# halloween-grave-bell-v02.net
KiCad netlist of a schematic drawn in EAGLE
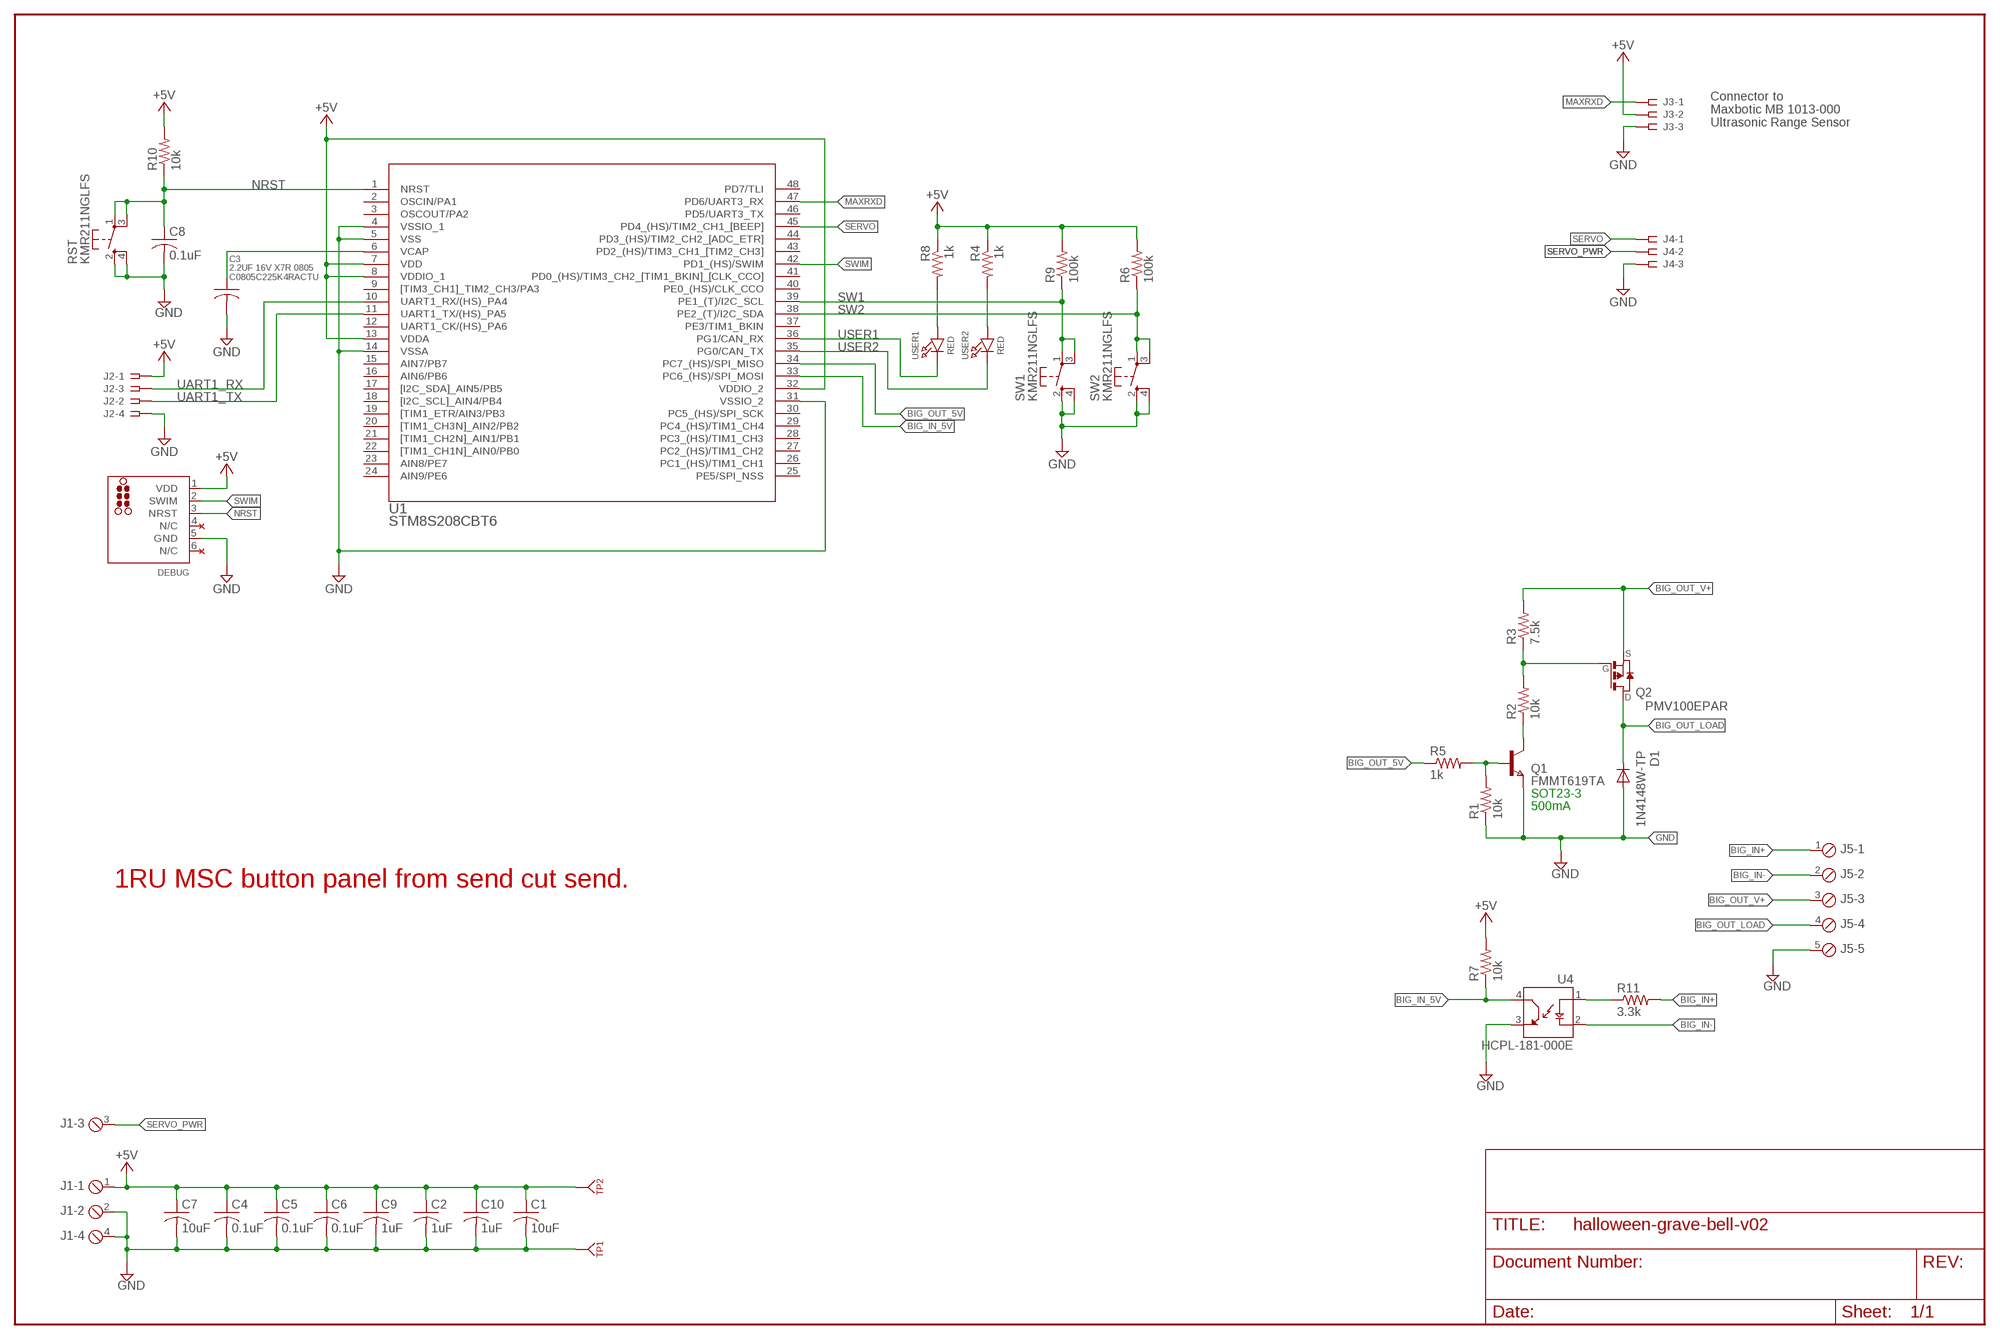
[diagram p0: schematic, sheet 1]

(export (version "E")
  (design (tool "Eeschema 10.0.6"))
  (components
    (comp (ref "C1")
      (value "10uF")
      (footprint "eagle-import:C1210")
      (fields (field (name "MFR") "KEMET") (field (name "MFR_PART_NO") "C1210C105K4PACTU"))
      (libsource (lib "eagle-import") (part "C-USC1210"))
    )
    (comp (ref "C2")
      (value "1uF")
      (footprint "eagle-import:C0603")
      (libsource (lib "eagle-import") (part "C-USC0603"))
    )
    (comp (ref "C3")
      (value "2.2UF 16V X7R 0805")
      (footprint "eagle-import:C0805")
      (fields (field (name "MFR_PART_NUM") "C0805C225K4RACTU"))
      (libsource (lib "eagle-import") (part "resistor_C-USC0805"))
    )
    (comp (ref "C4")
      (value "0.1uF")
      (footprint "eagle-import:C0603")
      (libsource (lib "eagle-import") (part "C-USC0603"))
    )
    (comp (ref "C5")
      (value "0.1uF")
      (footprint "eagle-import:C0603")
      (libsource (lib "eagle-import") (part "C-USC0603"))
    )
    (comp (ref "C6")
      (value "0.1uF")
      (footprint "eagle-import:C0603")
      (libsource (lib "eagle-import") (part "C-USC0603"))
    )
    (comp (ref "C7")
      (value "10uF")
      (footprint "eagle-import:C1210")
      (fields (field (name "MFR") "KEMET") (field (name "MFR_PART_NO") "C1210C105K4PACTU"))
      (libsource (lib "eagle-import") (part "C-USC1210"))
    )
    (comp (ref "C8")
      (value "0.1uF")
      (footprint "eagle-import:C0805")
      (libsource (lib "eagle-import") (part "C-USC0805"))
    )
    (comp (ref "C9")
      (value "1uF")
      (footprint "eagle-import:C0603")
      (libsource (lib "eagle-import") (part "C-USC0603"))
    )
    (comp (ref "C10")
      (value "1uF")
      (footprint "eagle-import:C0603")
      (libsource (lib "eagle-import") (part "C-USC0603"))
    )
    (comp (ref "D1")
      (value "1N4148W-TP")
      (footprint "eagle-import:SOD123")
      (libsource (lib "eagle-import") (part "DIODE-SOD123"))
    )
    (comp (ref "DEBUG")
      (value "TC2030-NL-STM8")
      (footprint "eagle-import:TC2030-NL")
      (libsource (lib "eagle-import") (part "TC2030-NL-STM8"))
    )
    (comp (ref "J1")
      (value "MPT4")
      (footprint "eagle-import:4POL254")
      (libsource (lib "eagle-import") (part "MPT4"))
    )
    (comp (ref "J2")
      (value "SSW-104-02-S-S")
      (footprint "eagle-import:SSW-104-02-S-S")
      (libsource (lib "eagle-import") (part "SSW-104-02-S-S"))
    )
    (comp (ref "J3")
      (value "SSW-103-02-S-S")
      (footprint "eagle-import:SSW-103-02-S-S")
      (libsource (lib "eagle-import") (part "SSW-103-02-S-S"))
    )
    (comp (ref "J4")
      (value "SSW-103-02-S-S")
      (footprint "eagle-import:SSW-103-02-S-S")
      (libsource (lib "eagle-import") (part "SSW-103-02-S-S"))
    )
    (comp (ref "J5")
      (value "MPT5")
      (footprint "eagle-import:5POL254")
      (libsource (lib "eagle-import") (part "MPT5"))
    )
    (comp (ref "Q1")
      (value "FMMT619TA")
      (footprint "eagle-import:SOT-23")
      (fields (field (name "MPN") "DSS20201L-7"))
      (libsource (lib "eagle-import") (part "NPNSOT23"))
    )
    (comp (ref "Q2")
      (value "PMOSSOT23")
      (footprint "eagle-import:SOT-23")
      (libsource (lib "eagle-import") (part "PMOSSOT23"))
    )
    (comp (ref "R1")
      (value "10k")
      (footprint "eagle-import:R0603")
      (libsource (lib "eagle-import") (part "R-US_R0603"))
    )
    (comp (ref "R2")
      (value "10k")
      (footprint "eagle-import:R0603")
      (libsource (lib "eagle-import") (part "R-US_R0603"))
    )
    (comp (ref "R3")
      (value "7.5k")
      (footprint "eagle-import:R0603")
      (libsource (lib "eagle-import") (part "R-US_R0603"))
    )
    (comp (ref "R4")
      (value "1k")
      (footprint "eagle-import:R0805")
      (libsource (lib "eagle-import") (part "R-US_R0805"))
    )
    (comp (ref "R5")
      (value "1k")
      (footprint "eagle-import:R0603")
      (libsource (lib "eagle-import") (part "R-US_R0603"))
    )
    (comp (ref "R6")
      (value "100k")
      (footprint "eagle-import:R0805")
      (libsource (lib "eagle-import") (part "R-US_R0805"))
    )
    (comp (ref "R7")
      (value "10k")
      (footprint "eagle-import:R0603")
      (libsource (lib "eagle-import") (part "R-US_R0603"))
    )
    (comp (ref "R8")
      (value "1k")
      (footprint "eagle-import:R0805")
      (libsource (lib "eagle-import") (part "R-US_R0805"))
    )
    (comp (ref "R9")
      (value "100k")
      (footprint "eagle-import:R0805")
      (libsource (lib "eagle-import") (part "R-US_R0805"))
    )
    (comp (ref "R10")
      (value "10k")
      (footprint "eagle-import:R0805")
      (libsource (lib "eagle-import") (part "R-US_R0805"))
    )
    (comp (ref "R11")
      (value "3.3k")
      (footprint "eagle-import:R0603")
      (libsource (lib "eagle-import") (part "R-US_R0603"))
    )
    (comp (ref "RST")
      (value "KMR211NGLFS")
      (footprint "eagle-import:KMR2")
      (libsource (lib "eagle-import") (part "SPST_TACT-KMR2"))
    )
    (comp (ref "SW1")
      (value "KMR211NGLFS")
      (footprint "eagle-import:KMR2")
      (libsource (lib "eagle-import") (part "SPST_TACT-KMR2"))
    )
    (comp (ref "SW2")
      (value "KMR211NGLFS")
      (footprint "eagle-import:KMR2")
      (libsource (lib "eagle-import") (part "SPST_TACT-KMR2"))
    )
    (comp (ref "TP1")
      (value "KEYSTONE_500X")
      (footprint "eagle-import:KEYSTONE_TP500X")
      (libsource (lib "eagle-import") (part "KEYSTONE_500X"))
    )
    (comp (ref "TP2")
      (value "KEYSTONE_500X")
      (footprint "eagle-import:KEYSTONE_TP500X")
      (libsource (lib "eagle-import") (part "KEYSTONE_500X"))
    )
    (comp (ref "U1")
      (value "STM8S208CBT6")
      (footprint "eagle-import:LQFP-48_STM")
      (libsource (lib "eagle-import") (part "STM8S208CBT6"))
    )
    (comp (ref "U4")
      (value "HCPL-181-000E")
      (footprint "eagle-import:SOIC254P675X240-4N")
      (fields (field (name "DIGI-KEY_PART_NUMBER") "516-1646-1-ND") (field (name "MF") "Broadcom Limited"))
      (libsource (lib "eagle-import") (part "HCPL-181-000E"))
    )
    (comp (ref "USER1")
      (value "RED")
      (footprint "eagle-import:CHIPLED_0805_NOOUTLINE")
      (libsource (lib "eagle-import") (part "LED0805_NOOUTLINE"))
    )
    (comp (ref "USER2")
      (value "RED")
      (footprint "eagle-import:CHIPLED_0805_NOOUTLINE")
      (libsource (lib "eagle-import") (part "LED0805_NOOUTLINE"))
    )
  )
  (nets
    (net (code "1") (name "+5V") (class "Default")
      (node (ref "C1") (pin "1") (pinfunction "1_1") (pintype "passive"))
      (node (ref "C10") (pin "1") (pinfunction "1_1") (pintype "passive"))
      (node (ref "C2") (pin "1") (pinfunction "1_1") (pintype "passive"))
      (node (ref "C4") (pin "1") (pinfunction "1_1") (pintype "passive"))
      (node (ref "C5") (pin "1") (pinfunction "1_1") (pintype "passive"))
      (node (ref "C6") (pin "1") (pinfunction "1_1") (pintype "passive"))
      (node (ref "C7") (pin "1") (pinfunction "1_1") (pintype "passive"))
      (node (ref "C9") (pin "1") (pinfunction "1_1") (pintype "passive"))
      (node (ref "DEBUG") (pin "1") (pinfunction "VDD_1") (pintype "passive"))
      (node (ref "J1") (pin "1") (pinfunction "1_1") (pintype "passive"))
      (node (ref "J2") (pin "1") (pinfunction "1_1") (pintype "passive"))
      (node (ref "J3") (pin "2") (pinfunction "1_2") (pintype "passive"))
      (node (ref "R10") (pin "2") (pinfunction "2_2") (pintype "passive"))
      (node (ref "R4") (pin "1") (pinfunction "1_1") (pintype "passive"))
      (node (ref "R6") (pin "2") (pinfunction "2_2") (pintype "passive"))
      (node (ref "R7") (pin "2") (pinfunction "2_2") (pintype "passive"))
      (node (ref "R8") (pin "1") (pinfunction "1_1") (pintype "passive"))
      (node (ref "R9") (pin "2") (pinfunction "2_2") (pintype "passive"))
      (node (ref "TP2") (pin "1") (pinfunction "P$1_1") (pintype "bidirectional"))
      (node (ref "U1") (pin "13") (pinfunction "VDDA_13") (pintype "power_in"))
      (node (ref "U1") (pin "32") (pinfunction "VDDIO_2_32") (pintype "power_in"))
      (node (ref "U1") (pin "7") (pinfunction "VDD_7") (pintype "power_in"))
      (node (ref "U1") (pin "8") (pinfunction "VDDIO_1_8") (pintype "power_in"))
    )
    (net (code "2") (name "/SW1") (class "Default")
      (node (ref "R9") (pin "1") (pinfunction "1_1") (pintype "passive"))
      (node (ref "SW1") (pin "1") (pinfunction "P_1") (pintype "passive"))
      (node (ref "SW1") (pin "3") (pinfunction "P1_3") (pintype "passive"))
      (node (ref "U1") (pin "39") (pinfunction "PE1_(T)/I2C_SCL_39") (pintype "bidirectional"))
    )
    (net (code "3") (name "/SW2") (class "Default")
      (node (ref "R6") (pin "1") (pinfunction "1_1") (pintype "passive"))
      (node (ref "SW2") (pin "1") (pinfunction "P_1") (pintype "passive"))
      (node (ref "SW2") (pin "3") (pinfunction "P1_3") (pintype "passive"))
      (node (ref "U1") (pin "38") (pinfunction "PE2_(T)/I2C_SDA_38") (pintype "bidirectional"))
    )
    (net (code "4") (name "/UART1_RX") (class "Default")
      (node (ref "J2") (pin "3") (pinfunction "1_3") (pintype "passive"))
      (node (ref "U1") (pin "10") (pinfunction "UART1_RX/(HS)_PA4_10") (pintype "bidirectional"))
    )
    (net (code "5") (name "/UART1_TX") (class "Default")
      (node (ref "J2") (pin "2") (pinfunction "1_2") (pintype "passive"))
      (node (ref "U1") (pin "11") (pinfunction "UART1_TX/(HS)_PA5_11") (pintype "bidirectional"))
    )
    (net (code "6") (name "/USER1") (class "Default")
      (node (ref "U1") (pin "36") (pinfunction "PG1/CAN_RX_36") (pintype "bidirectional"))
      (node (ref "USER1") (pin "C") (pinfunction "C_C") (pintype "passive"))
    )
    (net (code "7") (name "/USER2") (class "Default")
      (node (ref "U1") (pin "35") (pinfunction "PG0/CAN_TX_35") (pintype "bidirectional"))
      (node (ref "USER2") (pin "C") (pinfunction "C_C") (pintype "passive"))
    )
    (net (code "8") (name "BIG_IN+") (class "Default")
      (node (ref "J5") (pin "1") (pinfunction "1_1") (pintype "passive"))
      (node (ref "R11") (pin "2") (pinfunction "2_2") (pintype "passive"))
    )
    (net (code "9") (name "BIG_IN-") (class "Default")
      (node (ref "J5") (pin "2") (pinfunction "1_2") (pintype "passive"))
      (node (ref "U4") (pin "2") (pinfunction "CATHODE_2") (pintype "passive"))
    )
    (net (code "10") (name "BIG_IN_5V") (class "Default")
      (node (ref "R7") (pin "1") (pinfunction "1_1") (pintype "passive"))
      (node (ref "U1") (pin "33") (pinfunction "PC6_(HS)/SPI_MOSI_33") (pintype "bidirectional"))
      (node (ref "U4") (pin "4") (pinfunction "COLLECTOR_4") (pintype "passive"))
    )
    (net (code "11") (name "BIG_OUT_5V") (class "Default")
      (node (ref "R5") (pin "1") (pinfunction "1_1") (pintype "passive"))
      (node (ref "U1") (pin "34") (pinfunction "PC7_(HS)/SPI_MISO_34") (pintype "bidirectional"))
    )
    (net (code "12") (name "BIG_OUT_LOAD") (class "Default")
      (node (ref "D1") (pin "C") (pinfunction "C_C") (pintype "passive"))
      (node (ref "J5") (pin "4") (pinfunction "1_4") (pintype "passive"))
      (node (ref "Q2") (pin "1") (pinfunction "D_1") (pintype "passive"))
    )
    (net (code "13") (name "BIG_OUT_V+") (class "Default")
      (node (ref "J5") (pin "3") (pinfunction "1_3") (pintype "passive"))
      (node (ref "Q2") (pin "2") (pinfunction "S_2") (pintype "passive"))
      (node (ref "R3") (pin "2") (pinfunction "2_2") (pintype "passive"))
    )
    (net (code "14") (name "GND") (class "Default")
      (node (ref "C1") (pin "2") (pinfunction "2_2") (pintype "passive"))
      (node (ref "C10") (pin "2") (pinfunction "2_2") (pintype "passive"))
      (node (ref "C2") (pin "2") (pinfunction "2_2") (pintype "passive"))
      (node (ref "C3") (pin "2") (pinfunction "2_2") (pintype "passive"))
      (node (ref "C4") (pin "2") (pinfunction "2_2") (pintype "passive"))
      (node (ref "C5") (pin "2") (pinfunction "2_2") (pintype "passive"))
      (node (ref "C6") (pin "2") (pinfunction "2_2") (pintype "passive"))
      (node (ref "C7") (pin "2") (pinfunction "2_2") (pintype "passive"))
      (node (ref "C8") (pin "2") (pinfunction "2_2") (pintype "passive"))
      (node (ref "C9") (pin "2") (pinfunction "2_2") (pintype "passive"))
      (node (ref "D1") (pin "A") (pinfunction "A_A") (pintype "passive"))
      (node (ref "DEBUG") (pin "5") (pinfunction "GND_5") (pintype "output"))
      (node (ref "J1") (pin "2") (pinfunction "1_2") (pintype "passive"))
      (node (ref "J1") (pin "4") (pinfunction "1_4") (pintype "passive"))
      (node (ref "J2") (pin "4") (pinfunction "1_4") (pintype "passive"))
      (node (ref "J3") (pin "3") (pinfunction "1_3") (pintype "passive"))
      (node (ref "J4") (pin "3") (pinfunction "1_3") (pintype "passive"))
      (node (ref "J5") (pin "5") (pinfunction "1_5") (pintype "passive"))
      (node (ref "Q1") (pin "2") (pinfunction "E_2") (pintype "passive"))
      (node (ref "R1") (pin "1") (pinfunction "1_1") (pintype "passive"))
      (node (ref "RST") (pin "2") (pinfunction "S_2") (pintype "passive"))
      (node (ref "RST") (pin "4") (pinfunction "S1_4") (pintype "passive"))
      (node (ref "SW1") (pin "2") (pinfunction "S_2") (pintype "passive"))
      (node (ref "SW1") (pin "4") (pinfunction "S1_4") (pintype "passive"))
      (node (ref "SW2") (pin "2") (pinfunction "S_2") (pintype "passive"))
      (node (ref "SW2") (pin "4") (pinfunction "S1_4") (pintype "passive"))
      (node (ref "TP1") (pin "1") (pinfunction "P$1_1") (pintype "bidirectional"))
      (node (ref "U1") (pin "14") (pinfunction "VSSA_14") (pintype "power_in"))
      (node (ref "U1") (pin "31") (pinfunction "VSSIO_2_31") (pintype "power_in"))
      (node (ref "U1") (pin "4") (pinfunction "VSSIO_1_4") (pintype "power_in"))
      (node (ref "U1") (pin "5") (pinfunction "VSS_5") (pintype "power_in"))
      (node (ref "U4") (pin "3") (pinfunction "EMITTER_3") (pintype "passive"))
    )
    (net (code "15") (name "MAXRXD") (class "Default")
      (node (ref "J3") (pin "1") (pinfunction "1_1") (pintype "passive"))
      (node (ref "U1") (pin "47") (pinfunction "PD6/UART3_RX_47") (pintype "bidirectional"))
    )
    (net (code "16") (name "NRST") (class "Default")
      (node (ref "C8") (pin "1") (pinfunction "1_1") (pintype "passive"))
      (node (ref "DEBUG") (pin "3") (pinfunction "NRST_3") (pintype "power_in"))
      (node (ref "R10") (pin "1") (pinfunction "1_1") (pintype "passive"))
      (node (ref "RST") (pin "1") (pinfunction "P_1") (pintype "passive"))
      (node (ref "RST") (pin "3") (pinfunction "P1_3") (pintype "passive"))
      (node (ref "U1") (pin "1") (pinfunction "NRST_1") (pintype "bidirectional"))
    )
    (net (code "17") (name "Net-(Q1-B)") (class "Default")
      (node (ref "Q1") (pin "3") (pinfunction "B_3") (pintype "passive"))
      (node (ref "R1") (pin "2") (pinfunction "2_2") (pintype "passive"))
      (node (ref "R5") (pin "2") (pinfunction "2_2") (pintype "passive"))
    )
    (net (code "18") (name "Net-(Q1-C)") (class "Default")
      (node (ref "Q1") (pin "1") (pinfunction "C_1") (pintype "passive"))
      (node (ref "R2") (pin "1") (pinfunction "1_1") (pintype "passive"))
    )
    (net (code "19") (name "Net-(Q2-G)") (class "Default")
      (node (ref "Q2") (pin "3") (pinfunction "G_3") (pintype "passive"))
      (node (ref "R2") (pin "2") (pinfunction "2_2") (pintype "passive"))
      (node (ref "R3") (pin "1") (pinfunction "1_1") (pintype "passive"))
    )
    (net (code "20") (name "Net-(R4-Pad2)") (class "Default")
      (node (ref "R4") (pin "2") (pinfunction "2_2") (pintype "passive"))
      (node (ref "USER2") (pin "A") (pinfunction "A_A") (pintype "passive"))
    )
    (net (code "21") (name "Net-(R8-Pad2)") (class "Default")
      (node (ref "R8") (pin "2") (pinfunction "2_2") (pintype "passive"))
      (node (ref "USER1") (pin "A") (pinfunction "A_A") (pintype "passive"))
    )
    (net (code "22") (name "Net-(U1-VCAP)") (class "Default")
      (node (ref "C3") (pin "1") (pinfunction "1_1") (pintype "passive"))
      (node (ref "U1") (pin "6") (pinfunction "VCAP_6") (pintype "power_in"))
    )
    (net (code "23") (name "Net-(U4-ANODE)") (class "Default")
      (node (ref "R11") (pin "1") (pinfunction "1_1") (pintype "passive"))
      (node (ref "U4") (pin "1") (pinfunction "ANODE_1") (pintype "passive"))
    )
    (net (code "24") (name "SERVO") (class "Default")
      (node (ref "J4") (pin "1") (pinfunction "1_1") (pintype "passive"))
      (node (ref "U1") (pin "45") (pinfunction "PD4_(HS)/TIM2_CH1_[BEEP]_45") (pintype "passive"))
    )
    (net (code "25") (name "SERVO_PWR") (class "Default")
      (node (ref "J1") (pin "3") (pinfunction "1_3") (pintype "passive"))
      (node (ref "J4") (pin "2") (pinfunction "1_2") (pintype "passive"))
    )
    (net (code "26") (name "SWIM") (class "Default")
      (node (ref "DEBUG") (pin "2") (pinfunction "SWIM_2") (pintype "power_in"))
      (node (ref "U1") (pin "42") (pinfunction "PD1_(HS)/SWIM_42") (pintype "bidirectional"))
    )
    (net (code "27") (name "unconnected-(DEBUG-N{slash}C-Pad4)") (class "Default")
      (node (ref "DEBUG") (pin "4") (pinfunction "N/C_4") (pintype "bidirectional"))
    )
    (net (code "28") (name "unconnected-(DEBUG-N{slash}C-Pad6)") (class "Default")
      (node (ref "DEBUG") (pin "6") (pinfunction "N/C_6") (pintype "bidirectional"))
    )
    (net (code "29") (name "unconnected-(U1-AIN6{slash}PB6-Pad16)") (class "Default")
      (node (ref "U1") (pin "16") (pinfunction "AIN6/PB6_16") (pintype "bidirectional"))
    )
    (net (code "30") (name "unconnected-(U1-AIN7{slash}PB7-Pad15)") (class "Default")
      (node (ref "U1") (pin "15") (pinfunction "AIN7/PB7_15") (pintype "bidirectional"))
    )
    (net (code "31") (name "unconnected-(U1-AIN8{slash}PE7-Pad23)") (class "Default")
      (node (ref "U1") (pin "23") (pinfunction "AIN8/PE7_23") (pintype "bidirectional"))
    )
    (net (code "32") (name "unconnected-(U1-AIN9{slash}PE6-Pad24)") (class "Default")
      (node (ref "U1") (pin "24") (pinfunction "AIN9/PE6_24") (pintype "bidirectional"))
    )
    (net (code "33") (name "unconnected-(U1-OSCIN{slash}PA1-Pad2)") (class "Default")
      (node (ref "U1") (pin "2") (pinfunction "OSCIN/PA1_2") (pintype "bidirectional"))
    )
    (net (code "34") (name "unconnected-(U1-OSCOUT{slash}PA2-Pad3)") (class "Default")
      (node (ref "U1") (pin "3") (pinfunction "OSCOUT/PA2_3") (pintype "bidirectional"))
    )
    (net (code "35") (name "unconnected-(U1-PC1_(HS){slash}TIM1_CH1-Pad26)") (class "Default")
      (node (ref "U1") (pin "26") (pinfunction "PC1_(HS)/TIM1_CH1_26") (pintype "bidirectional"))
    )
    (net (code "36") (name "unconnected-(U1-PC2_(HS){slash}TIM1_CH2-Pad27)") (class "Default")
      (node (ref "U1") (pin "27") (pinfunction "PC2_(HS)/TIM1_CH2_27") (pintype "bidirectional"))
    )
    (net (code "37") (name "unconnected-(U1-PC3_(HS){slash}TIM1_CH3-Pad28)") (class "Default")
      (node (ref "U1") (pin "28") (pinfunction "PC3_(HS)/TIM1_CH3_28") (pintype "bidirectional"))
    )
    (net (code "38") (name "unconnected-(U1-PC4_(HS){slash}TIM1_CH4-Pad29)") (class "Default")
      (node (ref "U1") (pin "29") (pinfunction "PC4_(HS)/TIM1_CH4_29") (pintype "bidirectional"))
    )
    (net (code "39") (name "unconnected-(U1-PC5_(HS){slash}SPI_SCK-Pad30)") (class "Default")
      (node (ref "U1") (pin "30") (pinfunction "PC5_(HS)/SPI_SCK_30") (pintype "bidirectional"))
    )
    (net (code "40") (name "unconnected-(U1-PD0_(HS){slash}TIM3_CH2_[TIM1_BKIN]_[CLK_CCO]-Pad41)") (class "Default")
      (node (ref "U1") (pin "41") (pinfunction "PD0_(HS)/TIM3_CH2_[TIM1_BKIN]_[CLK_CCO]_41") (pintype "bidirectional"))
    )
    (net (code "41") (name "unconnected-(U1-PD2_(HS){slash}TIM3_CH1_[TIM2_CH3]-Pad43)") (class "Default")
      (node (ref "U1") (pin "43") (pinfunction "PD2_(HS)/TIM3_CH1_[TIM2_CH3]_43") (pintype "bidirectional"))
    )
    (net (code "42") (name "unconnected-(U1-PD3_(HS){slash}TIM2_CH2_[ADC_ETR]-Pad44)") (class "Default")
      (node (ref "U1") (pin "44") (pinfunction "PD3_(HS)/TIM2_CH2_[ADC_ETR]_44") (pintype "bidirectional"))
    )
    (net (code "43") (name "unconnected-(U1-PD5{slash}UART3_TX-Pad46)") (class "Default")
      (node (ref "U1") (pin "46") (pinfunction "PD5/UART3_TX_46") (pintype "bidirectional"))
    )
    (net (code "44") (name "unconnected-(U1-PD7{slash}TLI-Pad48)") (class "Default")
      (node (ref "U1") (pin "48") (pinfunction "PD7/TLI_48") (pintype "bidirectional"))
    )
    (net (code "45") (name "unconnected-(U1-PE0_(HS){slash}CLK_CCO-Pad40)") (class "Default")
      (node (ref "U1") (pin "40") (pinfunction "PE0_(HS)/CLK_CCO_40") (pintype "bidirectional"))
    )
    (net (code "46") (name "unconnected-(U1-PE3{slash}TIM1_BKIN-Pad37)") (class "Default")
      (node (ref "U1") (pin "37") (pinfunction "PE3/TIM1_BKIN_37") (pintype "bidirectional"))
    )
    (net (code "47") (name "unconnected-(U1-PE5{slash}SPI_NSS-Pad25)") (class "Default")
      (node (ref "U1") (pin "25") (pinfunction "PE5/SPI_NSS_25") (pintype "bidirectional"))
    )
    (net (code "48") (name "unconnected-(U1-UART1_CK{slash}(HS)_PA6-Pad12)") (class "Default")
      (node (ref "U1") (pin "12") (pinfunction "UART1_CK/(HS)_PA6_12") (pintype "bidirectional"))
    )
    (net (code "49") (name "unconnected-(U1-[I2C_SCL]_AIN4{slash}PB4-Pad18)") (class "Default")
      (node (ref "U1") (pin "18") (pinfunction "[I2C_SCL]_AIN4/PB4_18") (pintype "bidirectional"))
    )
    (net (code "50") (name "unconnected-(U1-[I2C_SDA]_AIN5{slash}PB5-Pad17)") (class "Default")
      (node (ref "U1") (pin "17") (pinfunction "[I2C_SDA]_AIN5/PB5_17") (pintype "bidirectional"))
    )
    (net (code "51") (name "unconnected-(U1-[TIM1_CH1N]_AIN0{slash}PB0-Pad22)") (class "Default")
      (node (ref "U1") (pin "22") (pinfunction "[TIM1_CH1N]_AIN0/PB0_22") (pintype "bidirectional"))
    )
    (net (code "52") (name "unconnected-(U1-[TIM1_CH2N]_AIN1{slash}PB1-Pad21)") (class "Default")
      (node (ref "U1") (pin "21") (pinfunction "[TIM1_CH2N]_AIN1/PB1_21") (pintype "bidirectional"))
    )
    (net (code "53") (name "unconnected-(U1-[TIM1_CH3N]_AIN2{slash}PB2-Pad20)") (class "Default")
      (node (ref "U1") (pin "20") (pinfunction "[TIM1_CH3N]_AIN2/PB2_20") (pintype "bidirectional"))
    )
    (net (code "54") (name "unconnected-(U1-[TIM1_ETR{slash}AIN3{slash}PB3-Pad19)") (class "Default")
      (node (ref "U1") (pin "19") (pinfunction "[TIM1_ETR/AIN3/PB3_19") (pintype "bidirectional"))
    )
    (net (code "55") (name "unconnected-(U1-[TIM3_CH1]_TIM2_CH3{slash}PA3-Pad9)") (class "Default")
      (node (ref "U1") (pin "9") (pinfunction "[TIM3_CH1]_TIM2_CH3/PA3_9") (pintype "bidirectional"))
    )
  )
)
